# Arduino_Nano_Countdown_Timer_7-seg_CC.net
KiCad netlist of a schematic drawn in EAGLE
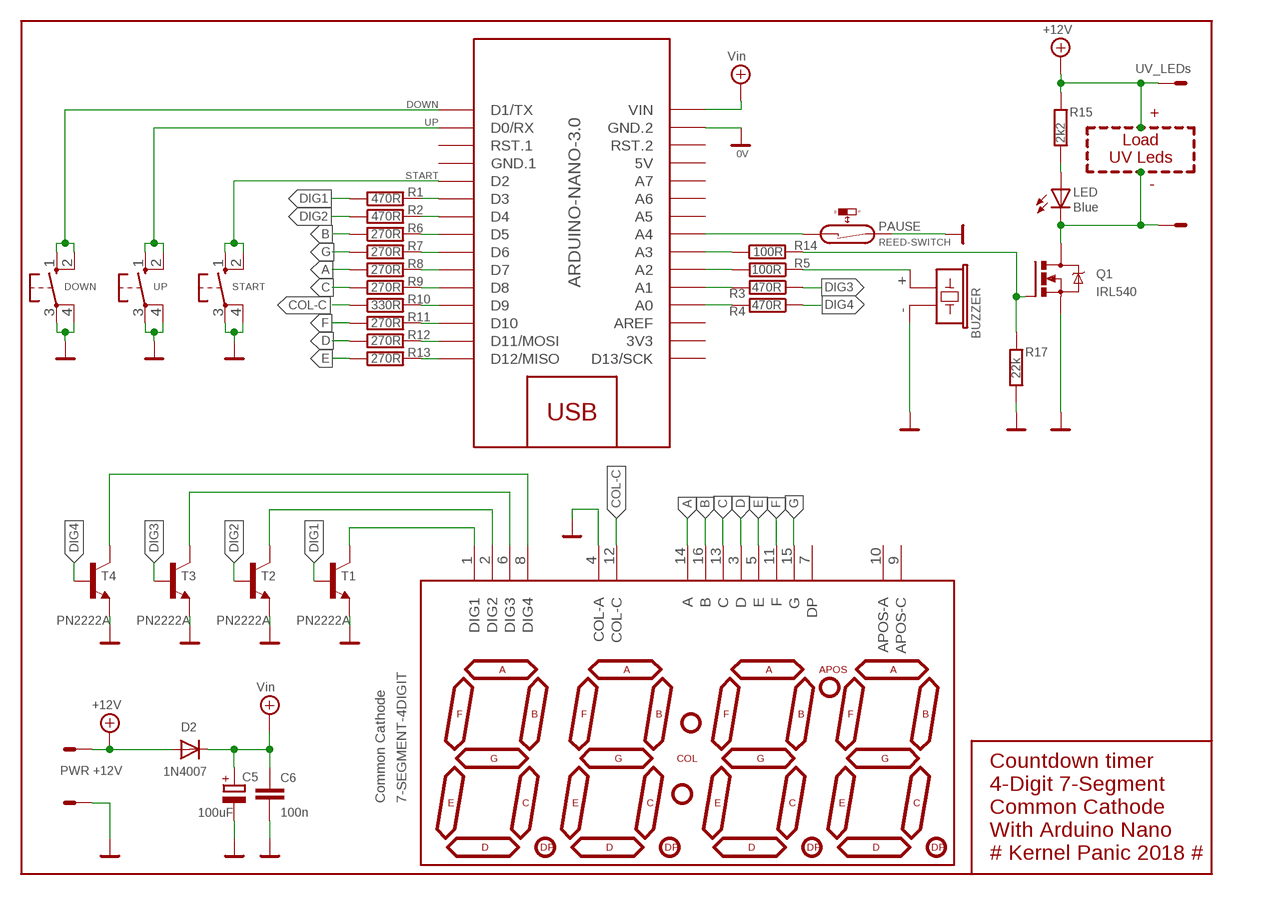
[diagram p0: schematic, sheet 1]

(export (version "E")
  (design (tool "Eeschema 10.0.6"))
  (components
    (comp (ref "BUZZER")
      (value "F/CM12P")
      (footprint "eagle-import:F_CM12P")
      (libsource (lib "eagle-import") (part "F/CM12P"))
    )
    (comp (ref "C5")
      (value "100uF")
      (footprint "eagle-import:E5-6.5")
      (libsource (lib "eagle-import") (part "CAPACITOR_POLE5-6.5"))
    )
    (comp (ref "C6")
      (value "100n")
      (footprint "eagle-import:C050-025X075")
      (libsource (lib "eagle-import") (part "CAPACITOR050-025X075"))
    )
    (comp (ref "D2")
      (value "1N4007")
      (footprint "eagle-import:DO41-10")
      (libsource (lib "eagle-import") (part "DIODE1N4004"))
    )
    (comp (ref "DOWN")
      (value "SWITCHE6K")
      (footprint "eagle-import:DTE6K")
      (libsource (lib "eagle-import") (part "SWITCHE6K"))
    )
    (comp (ref "LED")
      (value "Blue")
      (footprint "eagle-import:LED3MM")
      (libsource (lib "eagle-import") (part "LED3MM"))
    )
    (comp (ref "LED2")
      (value "7-SEGMENT-4DIGIT")
      (footprint "eagle-import:7-SEGMENT-4DIGIT")
      (libsource (lib "eagle-import") (part "7-SEGMENT-4DIGIT"))
    )
    (comp (ref "LOAD")
      (value "UV_LEDs")
      (footprint "eagle-import:22-23-2021")
      (fields (field (name "MF") "MOLEX") (field (name "MPN") "22-23-2021"))
      (libsource (lib "eagle-import") (part "22-23-2021"))
    )
    (comp (ref "M2")
      (value "ARDUINO-NANO-3.0")
      (footprint "eagle-import:ARDUINO-NANO-3.0")
      (libsource (lib "eagle-import") (part "ARDUINO-NANO-3.0"))
    )
    (comp (ref "PAUSE")
      (value "REED-SWITCH")
      (footprint "eagle-import:2PIN_HEADER")
      (libsource (lib "eagle-import") (part "REED-SWITCH-2PIN"))
    )
    (comp (ref "PWR")
      (value "PWR +12V")
      (footprint "eagle-import:22-23-2021")
      (fields (field (name "MF") "MOLEX") (field (name "MPN") "22-23-2021"))
      (libsource (lib "eagle-import") (part "22-23-2021"))
    )
    (comp (ref "Q1")
      (value "IRL540")
      (footprint "eagle-import:TO220BV")
      (libsource (lib "eagle-import") (part "IRF540"))
    )
    (comp (ref "R1")
      (value "470R")
      (footprint "eagle-import:R0805")
      (libsource (lib "eagle-import") (part "RESISTORR0805"))
    )
    (comp (ref "R2")
      (value "470R")
      (footprint "eagle-import:R0805")
      (libsource (lib "eagle-import") (part "RESISTORR0805"))
    )
    (comp (ref "R3")
      (value "470R")
      (footprint "eagle-import:R0805")
      (libsource (lib "eagle-import") (part "RESISTORR0805"))
    )
    (comp (ref "R4")
      (value "470R")
      (footprint "eagle-import:R0805")
      (libsource (lib "eagle-import") (part "RESISTORR0805"))
    )
    (comp (ref "R5")
      (value "100R")
      (footprint "eagle-import:R0805")
      (libsource (lib "eagle-import") (part "RESISTORR0805"))
    )
    (comp (ref "R6")
      (value "270R")
      (footprint "eagle-import:R0805")
      (libsource (lib "eagle-import") (part "RESISTORR0805"))
    )
    (comp (ref "R7")
      (value "270R")
      (footprint "eagle-import:R0805")
      (libsource (lib "eagle-import") (part "RESISTORR0805"))
    )
    (comp (ref "R8")
      (value "270R")
      (footprint "eagle-import:R0805")
      (libsource (lib "eagle-import") (part "RESISTORR0805"))
    )
    (comp (ref "R9")
      (value "270R")
      (footprint "eagle-import:R0805")
      (libsource (lib "eagle-import") (part "RESISTORR0805"))
    )
    (comp (ref "R10")
      (value "330R")
      (footprint "eagle-import:R0805")
      (libsource (lib "eagle-import") (part "RESISTORR0805"))
    )
    (comp (ref "R11")
      (value "270R")
      (footprint "eagle-import:R0805")
      (libsource (lib "eagle-import") (part "RESISTORR0805"))
    )
    (comp (ref "R12")
      (value "270R")
      (footprint "eagle-import:R0805")
      (libsource (lib "eagle-import") (part "RESISTORR0805"))
    )
    (comp (ref "R13")
      (value "270R")
      (footprint "eagle-import:R0805")
      (libsource (lib "eagle-import") (part "RESISTORR0805"))
    )
    (comp (ref "R14")
      (value "100R")
      (footprint "eagle-import:0207_10-8")
      (libsource (lib "eagle-import") (part "RESISTOR0207/10-OCTAGON"))
    )
    (comp (ref "R15")
      (value "2k2")
      (footprint "eagle-import:R0805")
      (libsource (lib "eagle-import") (part "RESISTORR0805"))
    )
    (comp (ref "R17")
      (value "22k")
      (footprint "eagle-import:R0805")
      (libsource (lib "eagle-import") (part "1_Stavros_RESISTORR0805"))
    )
    (comp (ref "START")
      (value "SWITCHE6K")
      (footprint "eagle-import:DTE6K")
      (libsource (lib "eagle-import") (part "SWITCHE6K"))
    )
    (comp (ref "T1")
      (value "PN2222A")
      (footprint "eagle-import:TO92-EBC-OVAL")
      (libsource (lib "eagle-import") (part "2N2222"))
    )
    (comp (ref "T2")
      (value "PN2222A")
      (footprint "eagle-import:TO92-EBC-OVAL")
      (libsource (lib "eagle-import") (part "2N2222"))
    )
    (comp (ref "T3")
      (value "PN2222A")
      (footprint "eagle-import:TO92-EBC-OVAL")
      (libsource (lib "eagle-import") (part "2N2222"))
    )
    (comp (ref "T4")
      (value "PN2222A")
      (footprint "eagle-import:TO92-EBC-OVAL")
      (libsource (lib "eagle-import") (part "2N2222"))
    )
    (comp (ref "UP")
      (value "SWITCHE6K")
      (footprint "eagle-import:DTE6K")
      (libsource (lib "eagle-import") (part "SWITCHE6K"))
    )
  )
  (nets
    (net (code "1") (name "+12V") (class "Default")
      (node (ref "D2") (pin "A") (pinfunction "A_A") (pintype "passive"))
      (node (ref "LOAD") (pin "1") (pinfunction "S_1") (pintype "passive"))
      (node (ref "PWR") (pin "2") (pinfunction "S_2") (pintype "passive"))
      (node (ref "R15") (pin "1") (pinfunction "1_1") (pintype "passive"))
    )
    (net (code "2") (name "/3V3") (class "Default")
      (node (ref "M2") (pin "J2.14") (pinfunction "3V3_J2.14") (pintype "power_in"))
    )
    (net (code "3") (name "/5V") (class "Default")
      (node (ref "M2") (pin "J2.4") (pinfunction "5V_J2.4") (pintype "power_in"))
    )
    (net (code "4") (name "/DOWN") (class "Default")
      (node (ref "DOWN") (pin "1") (pinfunction "S_1") (pintype "passive"))
      (node (ref "DOWN") (pin "2") (pinfunction "S_2") (pintype "passive"))
      (node (ref "M2") (pin "J1.1") (pinfunction "D1/TX_J1.1") (pintype "bidirectional"))
    )
    (net (code "5") (name "/GND.1") (class "Default")
      (node (ref "M2") (pin "J1.4") (pinfunction "GND.1_J1.4") (pintype "power_in"))
    )
    (net (code "6") (name "/START") (class "Default")
      (node (ref "M2") (pin "J1.5") (pinfunction "D2_J1.5") (pintype "bidirectional"))
      (node (ref "START") (pin "1") (pinfunction "S_1") (pintype "passive"))
      (node (ref "START") (pin "2") (pinfunction "S_2") (pintype "passive"))
    )
    (net (code "7") (name "/UP") (class "Default")
      (node (ref "M2") (pin "J1.2") (pinfunction "D0/RX_J1.2") (pintype "bidirectional"))
      (node (ref "UP") (pin "1") (pinfunction "S_1") (pintype "passive"))
      (node (ref "UP") (pin "2") (pinfunction "S_2") (pintype "passive"))
    )
    (net (code "8") (name "0V") (class "Default")
      (node (ref "BUZZER") (pin "-") (pinfunction "2_-") (pintype "passive"))
      (node (ref "C5") (pin "-") (pinfunction "-_-") (pintype "passive"))
      (node (ref "C6") (pin "2") (pinfunction "2_2") (pintype "passive"))
      (node (ref "DOWN") (pin "3") (pinfunction "P_3") (pintype "passive"))
      (node (ref "DOWN") (pin "4") (pinfunction "P_4") (pintype "passive"))
      (node (ref "LED2") (pin "4") (pinfunction "COL-A_4") (pintype "bidirectional"))
      (node (ref "M2") (pin "J2.2") (pinfunction "GND.2_J2.2") (pintype "power_in"))
      (node (ref "PAUSE") (pin "2") (pinfunction "2_2") (pintype "passive"))
      (node (ref "PWR") (pin "1") (pinfunction "S_1") (pintype "passive"))
      (node (ref "Q1") (pin "S") (pinfunction "S_S") (pintype "passive"))
      (node (ref "R17") (pin "2") (pinfunction "2_2") (pintype "passive"))
      (node (ref "START") (pin "3") (pinfunction "P_3") (pintype "passive"))
      (node (ref "START") (pin "4") (pinfunction "P_4") (pintype "passive"))
      (node (ref "T1") (pin "E") (pinfunction "E_E") (pintype "passive"))
      (node (ref "T2") (pin "E") (pinfunction "E_E") (pintype "passive"))
      (node (ref "T3") (pin "E") (pinfunction "E_E") (pintype "passive"))
      (node (ref "T4") (pin "E") (pinfunction "E_E") (pintype "passive"))
      (node (ref "UP") (pin "3") (pinfunction "P_3") (pintype "passive"))
      (node (ref "UP") (pin "4") (pinfunction "P_4") (pintype "passive"))
    )
    (net (code "9") (name "A") (class "Default")
      (node (ref "LED2") (pin "14") (pinfunction "A_14") (pintype "bidirectional"))
      (node (ref "R8") (pin "1") (pinfunction "1_1") (pintype "passive"))
    )
    (net (code "10") (name "B") (class "Default")
      (node (ref "LED2") (pin "16") (pinfunction "B_16") (pintype "bidirectional"))
      (node (ref "R6") (pin "1") (pinfunction "1_1") (pintype "passive"))
    )
    (net (code "11") (name "C") (class "Default")
      (node (ref "LED2") (pin "13") (pinfunction "C_13") (pintype "bidirectional"))
      (node (ref "R9") (pin "1") (pinfunction "1_1") (pintype "passive"))
    )
    (net (code "12") (name "COL-C") (class "Default")
      (node (ref "LED2") (pin "12") (pinfunction "COL-C_12") (pintype "bidirectional"))
      (node (ref "R10") (pin "1") (pinfunction "1_1") (pintype "passive"))
    )
    (net (code "13") (name "D") (class "Default")
      (node (ref "LED2") (pin "3") (pinfunction "D_3") (pintype "bidirectional"))
      (node (ref "R12") (pin "1") (pinfunction "1_1") (pintype "passive"))
    )
    (net (code "14") (name "DIG1") (class "Default")
      (node (ref "R1") (pin "1") (pinfunction "1_1") (pintype "passive"))
      (node (ref "T1") (pin "B") (pinfunction "B_B") (pintype "passive"))
    )
    (net (code "15") (name "DIG2") (class "Default")
      (node (ref "R2") (pin "1") (pinfunction "1_1") (pintype "passive"))
      (node (ref "T2") (pin "B") (pinfunction "B_B") (pintype "passive"))
    )
    (net (code "16") (name "DIG3") (class "Default")
      (node (ref "R3") (pin "1") (pinfunction "1_1") (pintype "passive"))
      (node (ref "T3") (pin "B") (pinfunction "B_B") (pintype "passive"))
    )
    (net (code "17") (name "DIG4") (class "Default")
      (node (ref "R4") (pin "1") (pinfunction "1_1") (pintype "passive"))
      (node (ref "T4") (pin "B") (pinfunction "B_B") (pintype "passive"))
    )
    (net (code "18") (name "E") (class "Default")
      (node (ref "LED2") (pin "5") (pinfunction "E_5") (pintype "bidirectional"))
      (node (ref "R13") (pin "1") (pinfunction "1_1") (pintype "passive"))
    )
    (net (code "19") (name "F") (class "Default")
      (node (ref "LED2") (pin "11") (pinfunction "F_11") (pintype "bidirectional"))
      (node (ref "R11") (pin "1") (pinfunction "1_1") (pintype "passive"))
    )
    (net (code "20") (name "G") (class "Default")
      (node (ref "LED2") (pin "15") (pinfunction "G_15") (pintype "bidirectional"))
      (node (ref "R7") (pin "1") (pinfunction "1_1") (pintype "passive"))
    )
    (net (code "21") (name "Net-(BUZZER-1)") (class "Default")
      (node (ref "BUZZER") (pin "+") (pinfunction "1_+") (pintype "passive"))
      (node (ref "R5") (pin "1") (pinfunction "1_1") (pintype "passive"))
    )
    (net (code "22") (name "Net-(LED-C)") (class "Default")
      (node (ref "LED") (pin "K") (pinfunction "C_K") (pintype "passive"))
      (node (ref "LOAD") (pin "2") (pinfunction "S_2") (pintype "passive"))
      (node (ref "Q1") (pin "D") (pinfunction "D_D") (pintype "passive"))
    )
    (net (code "23") (name "Net-(LED-PadA)") (class "Default")
      (node (ref "LED") (pin "A") (pinfunction "A_A") (pintype "passive"))
      (node (ref "R15") (pin "2") (pinfunction "2_2") (pintype "passive"))
    )
    (net (code "24") (name "Net-(LED2-DIG1)") (class "Default")
      (node (ref "LED2") (pin "1") (pinfunction "DIG1_1") (pintype "bidirectional"))
      (node (ref "T1") (pin "C") (pinfunction "C_C") (pintype "passive"))
    )
    (net (code "25") (name "Net-(LED2-DIG2)") (class "Default")
      (node (ref "LED2") (pin "2") (pinfunction "DIG2_2") (pintype "bidirectional"))
      (node (ref "T2") (pin "C") (pinfunction "C_C") (pintype "passive"))
    )
    (net (code "26") (name "Net-(LED2-DIG3)") (class "Default")
      (node (ref "LED2") (pin "6") (pinfunction "DIG3_6") (pintype "bidirectional"))
      (node (ref "T3") (pin "C") (pinfunction "C_C") (pintype "passive"))
    )
    (net (code "27") (name "Net-(LED2-DIG4)") (class "Default")
      (node (ref "LED2") (pin "8") (pinfunction "DIG4_8") (pintype "bidirectional"))
      (node (ref "T4") (pin "C") (pinfunction "C_C") (pintype "passive"))
    )
    (net (code "28") (name "Net-(M2-A0)") (class "Default")
      (node (ref "M2") (pin "J2.12") (pinfunction "A0_J2.12") (pintype "bidirectional"))
      (node (ref "R4") (pin "2") (pinfunction "2_2") (pintype "passive"))
    )
    (net (code "29") (name "Net-(M2-A1)") (class "Default")
      (node (ref "M2") (pin "J2.11") (pinfunction "A1_J2.11") (pintype "bidirectional"))
      (node (ref "R3") (pin "2") (pinfunction "2_2") (pintype "passive"))
    )
    (net (code "30") (name "Net-(M2-A2)") (class "Default")
      (node (ref "M2") (pin "J2.10") (pinfunction "A2_J2.10") (pintype "bidirectional"))
      (node (ref "R5") (pin "2") (pinfunction "2_2") (pintype "passive"))
    )
    (net (code "31") (name "Net-(M2-A3)") (class "Default")
      (node (ref "M2") (pin "J2.9") (pinfunction "A3_J2.9") (pintype "bidirectional"))
      (node (ref "R14") (pin "1") (pinfunction "1_1") (pintype "passive"))
    )
    (net (code "32") (name "Net-(M2-A4)") (class "Default")
      (node (ref "M2") (pin "J2.8") (pinfunction "A4_J2.8") (pintype "bidirectional"))
      (node (ref "PAUSE") (pin "1") (pinfunction "1_1") (pintype "passive"))
    )
    (net (code "33") (name "Net-(M2-D3)") (class "Default")
      (node (ref "M2") (pin "J1.6") (pinfunction "D3_J1.6") (pintype "bidirectional"))
      (node (ref "R1") (pin "2") (pinfunction "2_2") (pintype "passive"))
    )
    (net (code "34") (name "Net-(M2-D4)") (class "Default")
      (node (ref "M2") (pin "J1.7") (pinfunction "D4_J1.7") (pintype "bidirectional"))
      (node (ref "R2") (pin "2") (pinfunction "2_2") (pintype "passive"))
    )
    (net (code "35") (name "Net-(M2-D5)") (class "Default")
      (node (ref "M2") (pin "J1.8") (pinfunction "D5_J1.8") (pintype "bidirectional"))
      (node (ref "R6") (pin "2") (pinfunction "2_2") (pintype "passive"))
    )
    (net (code "36") (name "Net-(M2-D6)") (class "Default")
      (node (ref "M2") (pin "J1.9") (pinfunction "D6_J1.9") (pintype "bidirectional"))
      (node (ref "R7") (pin "2") (pinfunction "2_2") (pintype "passive"))
    )
    (net (code "37") (name "Net-(M2-D7)") (class "Default")
      (node (ref "M2") (pin "J1.10") (pinfunction "D7_J1.10") (pintype "bidirectional"))
      (node (ref "R8") (pin "2") (pinfunction "2_2") (pintype "passive"))
    )
    (net (code "38") (name "Net-(M2-D8)") (class "Default")
      (node (ref "M2") (pin "J1.11") (pinfunction "D8_J1.11") (pintype "bidirectional"))
      (node (ref "R9") (pin "2") (pinfunction "2_2") (pintype "passive"))
    )
    (net (code "39") (name "Net-(M2-D9)") (class "Default")
      (node (ref "M2") (pin "J1.12") (pinfunction "D9_J1.12") (pintype "bidirectional"))
      (node (ref "R10") (pin "2") (pinfunction "2_2") (pintype "passive"))
    )
    (net (code "40") (name "Net-(M2-D10)") (class "Default")
      (node (ref "M2") (pin "J1.13") (pinfunction "D10_J1.13") (pintype "bidirectional"))
      (node (ref "R11") (pin "2") (pinfunction "2_2") (pintype "passive"))
    )
    (net (code "41") (name "Net-(M2-D11{slash}MOSI)") (class "Default")
      (node (ref "M2") (pin "J1.14") (pinfunction "D11/MOSI_J1.14") (pintype "bidirectional"))
      (node (ref "R12") (pin "2") (pinfunction "2_2") (pintype "passive"))
    )
    (net (code "42") (name "Net-(M2-D12{slash}MISO)") (class "Default")
      (node (ref "M2") (pin "J1.15") (pinfunction "D12/MISO_J1.15") (pintype "bidirectional"))
      (node (ref "R13") (pin "2") (pinfunction "2_2") (pintype "passive"))
    )
    (net (code "43") (name "Net-(Q1-PadG)") (class "Default")
      (node (ref "Q1") (pin "G") (pinfunction "G_G") (pintype "passive"))
      (node (ref "R14") (pin "2") (pinfunction "2_2") (pintype "passive"))
      (node (ref "R17") (pin "1") (pinfunction "1_1") (pintype "passive"))
    )
    (net (code "44") (name "Vin") (class "Default")
      (node (ref "C5") (pin "+") (pinfunction "+_+") (pintype "passive"))
      (node (ref "C6") (pin "1") (pinfunction "1_1") (pintype "passive"))
      (node (ref "D2") (pin "C") (pinfunction "C_C") (pintype "passive"))
      (node (ref "M2") (pin "J2.1") (pinfunction "VIN_J2.1") (pintype "power_in"))
    )
    (net (code "45") (name "unconnected-(LED2-APOS-A-Pad10)") (class "Default")
      (node (ref "LED2") (pin "10") (pinfunction "APOS-A_10") (pintype "bidirectional"))
    )
    (net (code "46") (name "unconnected-(LED2-APOS-C-Pad9)") (class "Default")
      (node (ref "LED2") (pin "9") (pinfunction "APOS-C_9") (pintype "bidirectional"))
    )
    (net (code "47") (name "unconnected-(LED2-DP-Pad7)") (class "Default")
      (node (ref "LED2") (pin "7") (pinfunction "DP_7") (pintype "bidirectional"))
    )
    (net (code "48") (name "unconnected-(M2-A5-PadJ2.7)") (class "Default")
      (node (ref "M2") (pin "J2.7") (pinfunction "A5_J2.7") (pintype "bidirectional"))
    )
    (net (code "49") (name "unconnected-(M2-A6-PadJ2.6)") (class "Default")
      (node (ref "M2") (pin "J2.6") (pinfunction "A6_J2.6") (pintype "bidirectional"))
    )
    (net (code "50") (name "unconnected-(M2-A7-PadJ2.5)") (class "Default")
      (node (ref "M2") (pin "J2.5") (pinfunction "A7_J2.5") (pintype "bidirectional"))
    )
    (net (code "51") (name "unconnected-(M2-AREF-PadJ2.13)") (class "Default")
      (node (ref "M2") (pin "J2.13") (pinfunction "AREF_J2.13") (pintype "bidirectional"))
    )
    (net (code "52") (name "unconnected-(M2-D13{slash}SCK-PadJ2.15)") (class "Default")
      (node (ref "M2") (pin "J2.15") (pinfunction "D13/SCK_J2.15") (pintype "bidirectional"))
    )
    (net (code "53") (name "unconnected-(M2-RST.1-PadJ1.3)") (class "Default")
      (node (ref "M2") (pin "J1.3") (pinfunction "RST.1_J1.3") (pintype "bidirectional"))
    )
    (net (code "54") (name "unconnected-(M2-RST.2-PadJ2.3)") (class "Default")
      (node (ref "M2") (pin "J2.3") (pinfunction "RST.2_J2.3") (pintype "bidirectional"))
    )
  )
)
